# RFswitch.net
KiCad netlist of a schematic drawn in Altium Designer
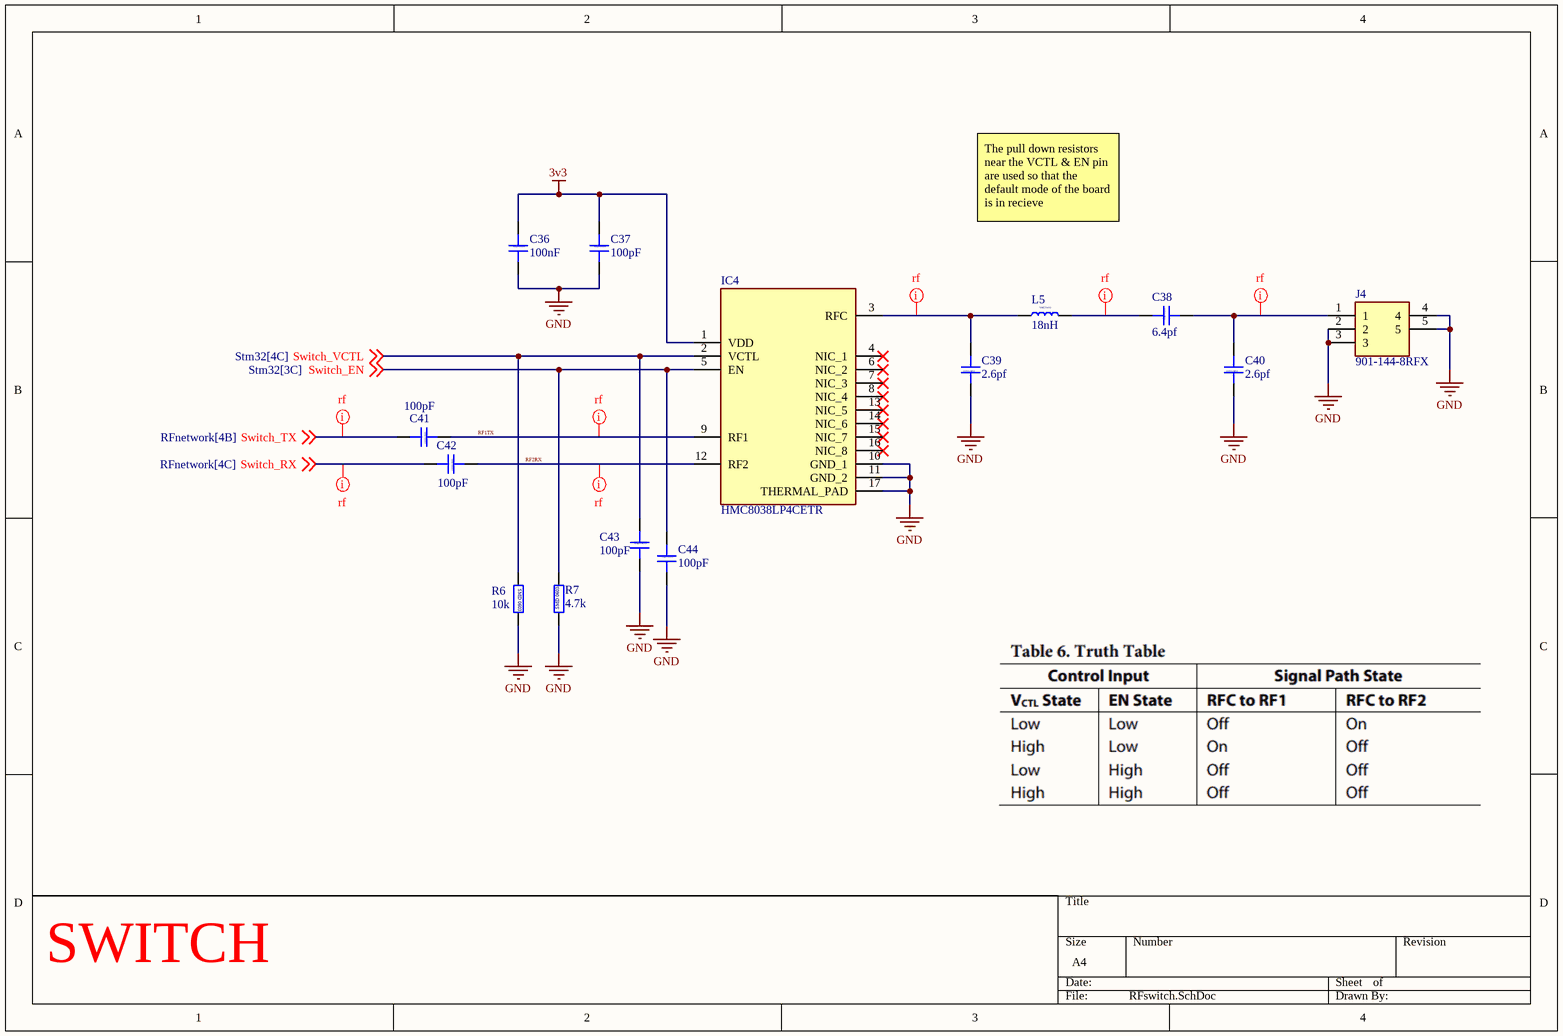
[diagram p0:  RFswitch.SchDoc]

(export (version "E")
  (design (tool "Eeschema 10.0.6"))
  (components
    (comp (ref "C36")
      (value "100nF")
      (footprint "CAP_0603")
      (description "Capacitor SMD 0603 RATED")
      (libsource (lib "STeRG-Passives-Standard") (part "Capacitor-SMD-0603"))
    )
    (comp (ref "C37")
      (value "100pF")
      (footprint "CAP_0603")
      (description "Capacitor SMD 0603 RATED")
      (libsource (lib "STeRG-Passives-Standard") (part "Capacitor-SMD-0603"))
    )
    (comp (ref "C38")
      (value "6.4pf")
      (footprint "CAP_0402")
      (description "Capacitor SMD 0402 RATED")
      (libsource (lib "STeRG-Passives-Standard") (part "Capacitor-SMD-0402"))
    )
    (comp (ref "C39")
      (value "2.6pf")
      (footprint "CAP_0402")
      (description "Capacitor SMD 0402 RATED")
      (libsource (lib "STeRG-Passives-Standard") (part "Capacitor-SMD-0402"))
    )
    (comp (ref "C40")
      (value "2.6pf")
      (footprint "CAP_0402")
      (description "Capacitor SMD 0402 RATED")
      (libsource (lib "STeRG-Passives-Standard") (part "Capacitor-SMD-0402"))
    )
    (comp (ref "C41")
      (value "100pF")
      (footprint "CAP_0603")
      (description "Capacitor SMD 0603 RATED")
      (libsource (lib "STeRG-Passives-Standard") (part "Capacitor-SMD-0603"))
    )
    (comp (ref "C42")
      (value "100pF")
      (footprint "CAP_0603")
      (description "Capacitor SMD 0603 RATED")
      (libsource (lib "STeRG-Passives-Standard") (part "Capacitor-SMD-0603"))
    )
    (comp (ref "C43")
      (value "100pF")
      (footprint "CAP_0603")
      (description "Capacitor SMD 0603 RATED")
      (libsource (lib "STeRG-Passives-Standard") (part "Capacitor-SMD-0603"))
    )
    (comp (ref "C44")
      (value "100pF")
      (footprint "CAP_0603")
      (description "Capacitor SMD 0603 RATED")
      (libsource (lib "STeRG-Passives-Standard") (part "Capacitor-SMD-0603"))
    )
    (comp (ref "IC4")
      (value "HMC8038LP4CETR")
      (footprint "SamacSys:QFN65P400X400X90-17N-D")
      (description "Integrated Circuit")
      (fields (field (name "MOUSER PART NUMBER") "584-HMC8038LP4CETR"))
      (libsource (lib "SamacSys") (part "HMC8038LP4CETR"))
    )
    (comp (ref "J4")
      (value "901-144-8RFX")
      (footprint "9011448RFX")
      (description "AMPHENOL RF - 901-144-8RFX - RF / Coaxial Connector")
      (fields (field (name "MOUSER PART NUMBER") "523-901-144-8RFX"))
      (libsource (lib "SamacSys") (part "901-144-8RFX"))
    )
    (comp (ref "L5")
      (value "18nH")
      (footprint "IND_0402")
      (description "Inductor SMD 0402")
      (libsource (lib "STeRG-Passives-Standard") (part "Inductor-SMD-RF-0402"))
    )
    (comp (ref "R6")
      (value "10k")
      (footprint "RES_0603")
      (description "Resistor SMD 0603 RATED")
      (libsource (lib "STeRG-Passives-Standard") (part "Resistor-SMD-0603"))
    )
    (comp (ref "R7")
      (value "4.7k")
      (footprint "RES_0603")
      (description "Resistor SMD 0603 RATED")
      (libsource (lib "STeRG-Passives-Standard") (part "Resistor-SMD-0603"))
    )
  )
  (nets
    (net (code "1") (name "/RF1TX") (class "Default")
      (node (ref "C41") (pin "1") (pinfunction "1_1") (pintype "passive"))
      (node (ref "IC4") (pin "9") (pinfunction "RF1_9") (pintype "passive"))
    )
    (net (code "2") (name "/RF2RX") (class "Default")
      (node (ref "C42") (pin "1") (pinfunction "1_1") (pintype "passive"))
      (node (ref "IC4") (pin "12") (pinfunction "RF2_12") (pintype "passive"))
    )
    (net (code "3") (name "3v3") (class "Default")
      (node (ref "C36") (pin "1") (pinfunction "1_1") (pintype "passive"))
      (node (ref "C37") (pin "1") (pinfunction "1_1") (pintype "passive"))
      (node (ref "IC4") (pin "1") (pinfunction "VDD_1") (pintype "passive"))
    )
    (net (code "4") (name "GND") (class "Default")
      (node (ref "C36") (pin "2") (pinfunction "2_2") (pintype "passive"))
      (node (ref "C37") (pin "2") (pinfunction "2_2") (pintype "passive"))
      (node (ref "C39") (pin "1") (pinfunction "1_1") (pintype "passive"))
      (node (ref "C40") (pin "1") (pinfunction "1_1") (pintype "passive"))
      (node (ref "C43") (pin "2") (pinfunction "2_2") (pintype "passive"))
      (node (ref "C44") (pin "2") (pinfunction "2_2") (pintype "passive"))
      (node (ref "IC4") (pin "10") (pinfunction "GND_1_10") (pintype "passive"))
      (node (ref "IC4") (pin "11") (pinfunction "GND_2_11") (pintype "passive"))
      (node (ref "IC4") (pin "17") (pinfunction "THERMAL_PAD_17") (pintype "passive"))
      (node (ref "J4") (pin "2") (pinfunction "2_2") (pintype "passive"))
      (node (ref "J4") (pin "3") (pinfunction "3_3") (pintype "passive"))
      (node (ref "J4") (pin "4") (pinfunction "4_4") (pintype "passive"))
      (node (ref "J4") (pin "5") (pinfunction "5_5") (pintype "passive"))
      (node (ref "R6") (pin "2") (pinfunction "2_2") (pintype "passive"))
      (node (ref "R7") (pin "1") (pinfunction "1_1") (pintype "passive"))
    )
    (net (code "5") (name "Net-(C38-Pad1)") (class "Default")
      (node (ref "C38") (pin "1") (pinfunction "1_1") (pintype "passive"))
      (node (ref "L5") (pin "2") (pinfunction "2_2") (pintype "passive"))
    )
    (net (code "6") (name "Net-(C38-Pad2)") (class "Default")
      (node (ref "C38") (pin "2") (pinfunction "2_2") (pintype "passive"))
      (node (ref "C40") (pin "2") (pinfunction "2_2") (pintype "passive"))
      (node (ref "J4") (pin "1") (pinfunction "1_1") (pintype "passive"))
    )
    (net (code "7") (name "Net-(IC4-RFC)") (class "Default")
      (node (ref "C39") (pin "2") (pinfunction "2_2") (pintype "passive"))
      (node (ref "IC4") (pin "3") (pinfunction "RFC_3") (pintype "passive"))
      (node (ref "L5") (pin "1") (pinfunction "1_1") (pintype "passive"))
    )
    (net (code "8") (name "Switch_EN") (class "Default")
      (node (ref "C44") (pin "1") (pinfunction "1_1") (pintype "passive"))
      (node (ref "IC4") (pin "5") (pinfunction "EN_5") (pintype "passive"))
      (node (ref "R7") (pin "2") (pinfunction "2_2") (pintype "passive"))
    )
    (net (code "9") (name "Switch_RX") (class "Default")
      (node (ref "C42") (pin "2") (pinfunction "2_2") (pintype "passive"))
    )
    (net (code "10") (name "Switch_TX") (class "Default")
      (node (ref "C41") (pin "2") (pinfunction "2_2") (pintype "passive"))
    )
    (net (code "11") (name "Switch_VCTL") (class "Default")
      (node (ref "C43") (pin "1") (pinfunction "1_1") (pintype "passive"))
      (node (ref "IC4") (pin "2") (pinfunction "VCTL_2") (pintype "passive"))
      (node (ref "R6") (pin "1") (pinfunction "1_1") (pintype "passive"))
    )
    (net (code "12") (name "unconnected-(IC4-NIC_1-Pad4)") (class "Default")
      (node (ref "IC4") (pin "4") (pinfunction "NIC_1_4") (pintype "passive+no_connect"))
    )
    (net (code "13") (name "unconnected-(IC4-NIC_2-Pad6)") (class "Default")
      (node (ref "IC4") (pin "6") (pinfunction "NIC_2_6") (pintype "passive+no_connect"))
    )
    (net (code "14") (name "unconnected-(IC4-NIC_3-Pad7)") (class "Default")
      (node (ref "IC4") (pin "7") (pinfunction "NIC_3_7") (pintype "passive+no_connect"))
    )
    (net (code "15") (name "unconnected-(IC4-NIC_4-Pad8)") (class "Default")
      (node (ref "IC4") (pin "8") (pinfunction "NIC_4_8") (pintype "passive+no_connect"))
    )
    (net (code "16") (name "unconnected-(IC4-NIC_5-Pad13)") (class "Default")
      (node (ref "IC4") (pin "13") (pinfunction "NIC_5_13") (pintype "passive+no_connect"))
    )
    (net (code "17") (name "unconnected-(IC4-NIC_6-Pad14)") (class "Default")
      (node (ref "IC4") (pin "14") (pinfunction "NIC_6_14") (pintype "passive+no_connect"))
    )
    (net (code "18") (name "unconnected-(IC4-NIC_7-Pad15)") (class "Default")
      (node (ref "IC4") (pin "15") (pinfunction "NIC_7_15") (pintype "passive+no_connect"))
    )
    (net (code "19") (name "unconnected-(IC4-NIC_8-Pad16)") (class "Default")
      (node (ref "IC4") (pin "16") (pinfunction "NIC_8_16") (pintype "passive+no_connect"))
    )
  )
)
